# UV_Sterlizer.net
KiCad netlist of a schematic drawn in EAGLE
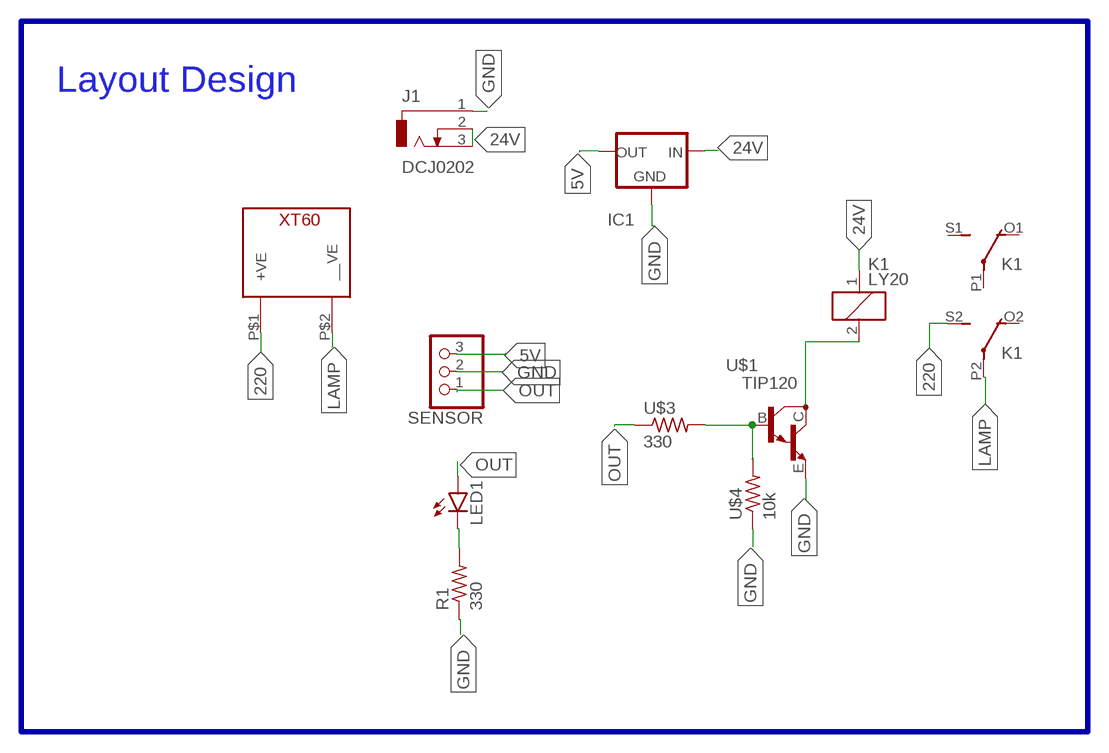
[diagram p0: schematic, sheet 1]

(export (version "E")
  (design (tool "Eeschema 10.0.6"))
  (components
    (comp (ref "IC1")
      (value "78XX-METAL")
      (footprint "eagle-import:TO3-79")
      (libsource (lib "eagle-import") (part "78XX-METAL"))
    )
    (comp (ref "J1")
      (value "DCJ0202")
      (footprint "eagle-import:DCJ0202")
      (libsource (lib "eagle-import") (part "DCJ0202"))
    )
    (comp (ref "K1")
      (value "LY20")
      (footprint "eagle-import:LY20")
      (libsource (lib "eagle-import") (part "LY20"))
    )
    (comp (ref "LED1")
      (value "LED5MM")
      (footprint "eagle-import:LED5MM")
      (libsource (lib "eagle-import") (part "LED5MM"))
    )
    (comp (ref "R1")
      (value "330")
      (footprint "eagle-import:0204_7")
      (libsource (lib "eagle-import") (part "R-US_0204/7"))
    )
    (comp (ref "SENSOR")
      (value "PINHD-1X3")
      (footprint "eagle-import:1X03")
      (libsource (lib "eagle-import") (part "PINHD-1X3"))
    )
    (comp (ref "U$1")
      (value "TIP120")
      (footprint "eagle-import:TIP120")
      (libsource (lib "eagle-import") (part "TIP120"))
    )
    (comp (ref "U$3")
      (value "330")
      (footprint "eagle-import:0207_10")
      (libsource (lib "eagle-import") (part "RES-10"))
    )
    (comp (ref "U$4")
      (value "10k")
      (footprint "eagle-import:0207_10")
      (libsource (lib "eagle-import") (part "RES-10"))
    )
    (comp (ref "U$5")
      (value "XT60_CONNECTOR")
      (footprint "eagle-import:XT60")
      (libsource (lib "eagle-import") (part "XT60_CONNECTOR"))
    )
  )
  (nets
    (net (code "1") (name "5V") (class "Default")
      (node (ref "IC1") (pin "1") (pinfunction "OUT_1") (pintype "passive"))
      (node (ref "SENSOR") (pin "3") (pinfunction "3_3") (pintype "passive"))
    )
    (net (code "2") (name "24V") (class "Default")
      (node (ref "IC1") (pin "3") (pinfunction "IN_3") (pintype "input"))
      (node (ref "J1") (pin "2") (pinfunction "2_2") (pintype "passive"))
      (node (ref "J1") (pin "3") (pinfunction "3_3") (pintype "passive"))
      (node (ref "K1") (pin "1") (pinfunction "1_1") (pintype "passive"))
    )
    (net (code "3") (name "220") (class "Default")
      (node (ref "K1") (pin "S2") (pinfunction "S_S2") (pintype "passive"))
      (node (ref "U$5") (pin "P$1") (pinfunction "+VE_P$1") (pintype "bidirectional"))
    )
    (net (code "4") (name "GND") (class "Default")
      (node (ref "IC1") (pin "2") (pinfunction "GND_2") (pintype "input"))
      (node (ref "J1") (pin "1") (pinfunction "1_1") (pintype "passive"))
      (node (ref "R1") (pin "1") (pinfunction "1_1") (pintype "passive"))
      (node (ref "SENSOR") (pin "2") (pinfunction "2_2") (pintype "passive"))
      (node (ref "U$1") (pin "E") (pinfunction "E_E") (pintype "passive"))
      (node (ref "U$4") (pin "1") (pinfunction "1_1") (pintype "passive"))
    )
    (net (code "5") (name "LAMP") (class "Default")
      (node (ref "K1") (pin "P2") (pinfunction "P_P2") (pintype "passive"))
      (node (ref "U$5") (pin "P$2") (pinfunction "__VE_P$2") (pintype "bidirectional"))
    )
    (net (code "6") (name "Net-(K1-Pad2)") (class "Default")
      (node (ref "K1") (pin "2") (pinfunction "2_2") (pintype "passive"))
      (node (ref "U$1") (pin "C") (pinfunction "C_C") (pintype "passive"))
    )
    (net (code "7") (name "Net-(LED1-C)") (class "Default")
      (node (ref "LED1") (pin "K") (pinfunction "C_K") (pintype "passive"))
      (node (ref "R1") (pin "2") (pinfunction "2_2") (pintype "passive"))
    )
    (net (code "8") (name "Net-(U$1-PadB)") (class "Default")
      (node (ref "U$1") (pin "B") (pinfunction "B_B") (pintype "passive"))
      (node (ref "U$3") (pin "2") (pinfunction "2_2") (pintype "passive"))
      (node (ref "U$4") (pin "2") (pinfunction "2_2") (pintype "passive"))
    )
    (net (code "9") (name "OUT") (class "Default")
      (node (ref "LED1") (pin "A") (pinfunction "A_A") (pintype "passive"))
      (node (ref "SENSOR") (pin "1") (pinfunction "1_1") (pintype "passive"))
      (node (ref "U$3") (pin "1") (pinfunction "1_1") (pintype "passive"))
    )
    (net (code "10") (name "unconnected-(K1B-O-PadO1)") (class "Default")
      (node (ref "K1") (pin "O1") (pinfunction "O_O1") (pintype "passive"))
    )
    (net (code "11") (name "unconnected-(K1B-P-PadP1)") (class "Default")
      (node (ref "K1") (pin "P1") (pinfunction "P_P1") (pintype "passive"))
    )
    (net (code "12") (name "unconnected-(K1B-S-PadS1)") (class "Default")
      (node (ref "K1") (pin "S1") (pinfunction "S_S1") (pintype "passive"))
    )
    (net (code "13") (name "unconnected-(K1C-O-PadO2)") (class "Default")
      (node (ref "K1") (pin "O2") (pinfunction "O_O2") (pintype "passive"))
    )
  )
)
